# BB-8_Dome_FX_Module.net
KiCad netlist of a schematic drawn in EAGLE
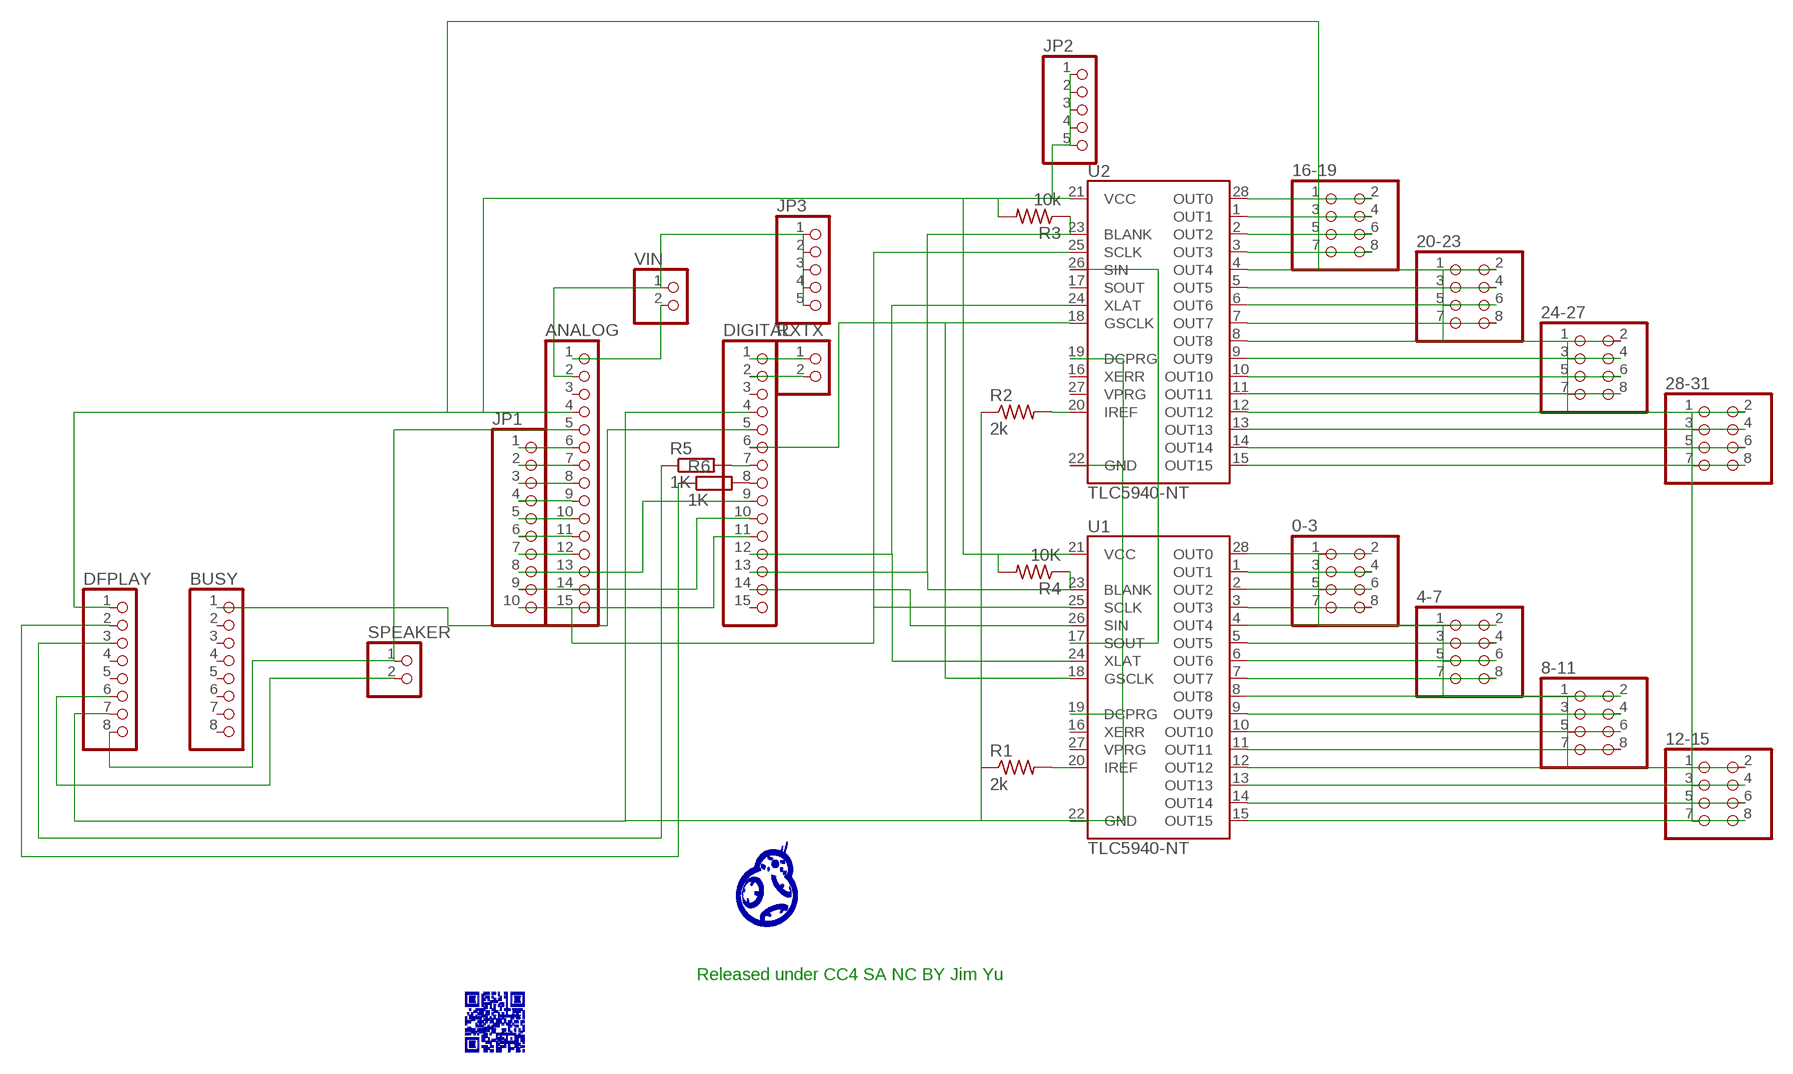
[diagram p0: schematic, sheet 1]

(export (version "E")
  (design (tool "Eeschema 10.0.6"))
  (components
    (comp (ref "0-3")
      (value "PINHD-2X4")
      (footprint "eagle-import:2X04")
      (libsource (lib "eagle-import") (part "PINHD-2X4"))
    )
    (comp (ref "4-7")
      (value "PINHD-2X4")
      (footprint "eagle-import:2X04")
      (libsource (lib "eagle-import") (part "PINHD-2X4"))
    )
    (comp (ref "8-11")
      (value "PINHD-2X4")
      (footprint "eagle-import:2X04")
      (libsource (lib "eagle-import") (part "PINHD-2X4"))
    )
    (comp (ref "12-15")
      (value "PINHD-2X4")
      (footprint "eagle-import:2X04")
      (libsource (lib "eagle-import") (part "PINHD-2X4"))
    )
    (comp (ref "16-19")
      (value "PINHD-2X4")
      (footprint "eagle-import:2X04")
      (libsource (lib "eagle-import") (part "PINHD-2X4"))
    )
    (comp (ref "20-23")
      (value "PINHD-2X4")
      (footprint "eagle-import:2X04")
      (libsource (lib "eagle-import") (part "PINHD-2X4"))
    )
    (comp (ref "24-27")
      (value "PINHD-2X4")
      (footprint "eagle-import:2X04")
      (libsource (lib "eagle-import") (part "PINHD-2X4"))
    )
    (comp (ref "28-31")
      (value "PINHD-2X4")
      (footprint "eagle-import:2X04")
      (libsource (lib "eagle-import") (part "PINHD-2X4"))
    )
    (comp (ref "ANALOG")
      (value "PINHD-1X15")
      (footprint "eagle-import:1X15")
      (libsource (lib "eagle-import") (part "PINHD-1X15"))
    )
    (comp (ref "BUSY")
      (value "PINHD-1X8")
      (footprint "eagle-import:1X08")
      (libsource (lib "eagle-import") (part "PINHD-1X8"))
    )
    (comp (ref "DFPLAY")
      (value "PINHD-1X8")
      (footprint "eagle-import:1X08")
      (libsource (lib "eagle-import") (part "PINHD-1X8"))
    )
    (comp (ref "DIGITAL")
      (value "PINHD-1X15")
      (footprint "eagle-import:1X15")
      (libsource (lib "eagle-import") (part "PINHD-1X15"))
    )
    (comp (ref "JP1")
      (value "PINHD-1X10")
      (footprint "eagle-import:1X10")
      (libsource (lib "eagle-import") (part "PINHD-1X10"))
    )
    (comp (ref "JP2")
      (value "PINHD-1X5")
      (footprint "eagle-import:1X05")
      (libsource (lib "eagle-import") (part "PINHD-1X5"))
    )
    (comp (ref "JP3")
      (value "PINHD-1X5")
      (footprint "eagle-import:1X05")
      (libsource (lib "eagle-import") (part "PINHD-1X5"))
    )
    (comp (ref "R1")
      (value "2k")
      (footprint "eagle-import:0204_5")
      (libsource (lib "eagle-import") (part "R-US_0204/5"))
    )
    (comp (ref "R2")
      (value "2k")
      (footprint "eagle-import:0204_5")
      (libsource (lib "eagle-import") (part "R-US_0204/5"))
    )
    (comp (ref "R3")
      (value "10k")
      (footprint "eagle-import:0204_5")
      (libsource (lib "eagle-import") (part "R-US_0204/5"))
    )
    (comp (ref "R4")
      (value "10K")
      (footprint "eagle-import:0204_5")
      (libsource (lib "eagle-import") (part "R-US_0204/5"))
    )
    (comp (ref "R5")
      (value "1K")
      (footprint "eagle-import:0204_5")
      (libsource (lib "eagle-import") (part "R-EU_0204/5"))
    )
    (comp (ref "R6")
      (value "1K")
      (footprint "eagle-import:0204_5")
      (libsource (lib "eagle-import") (part "R-EU_0204/5"))
    )
    (comp (ref "RXTX")
      (value "PINHD-1X2")
      (footprint "eagle-import:1X02")
      (libsource (lib "eagle-import") (part "PINHD-1X2"))
    )
    (comp (ref "SPEAKER")
      (value "PINHD-1X2")
      (footprint "eagle-import:1X02")
      (libsource (lib "eagle-import") (part "PINHD-1X2"))
    )
    (comp (ref "U1")
      (value "TLC5940-NT")
      (footprint "eagle-import:DIL28-3")
      (libsource (lib "eagle-import") (part "TLC5940-NT"))
    )
    (comp (ref "U2")
      (value "TLC5940-NT")
      (footprint "eagle-import:DIL28-3")
      (libsource (lib "eagle-import") (part "TLC5940-NT"))
    )
    (comp (ref "VIN")
      (value "PINHD-1X2")
      (footprint "eagle-import:1X02")
      (libsource (lib "eagle-import") (part "PINHD-1X2"))
    )
  )
  (nets
    (net (code "1") (name "Net-(ANALOG-Pad1)") (class "Default")
      (node (ref "ANALOG") (pin "1") (pinfunction "1_1") (pintype "passive"))
      (node (ref "VIN") (pin "2") (pinfunction "2_2") (pintype "passive"))
    )
    (net (code "2") (name "Net-(ANALOG-Pad2)") (class "Default")
      (node (ref "ANALOG") (pin "2") (pinfunction "2_2") (pintype "passive"))
      (node (ref "JP3") (pin "1") (pinfunction "1_1") (pintype "passive"))
      (node (ref "JP3") (pin "2") (pinfunction "2_2") (pintype "passive"))
      (node (ref "JP3") (pin "3") (pinfunction "3_3") (pintype "passive"))
      (node (ref "JP3") (pin "4") (pinfunction "4_4") (pintype "passive"))
      (node (ref "JP3") (pin "5") (pinfunction "5_5") (pintype "passive"))
      (node (ref "VIN") (pin "1") (pinfunction "1_1") (pintype "passive"))
    )
    (net (code "3") (name "Net-(ANALOG-Pad5)") (class "Default")
      (node (ref "ANALOG") (pin "5") (pinfunction "5_5") (pintype "passive"))
      (node (ref "DFPLAY") (pin "8") (pinfunction "8_8") (pintype "passive"))
      (node (ref "SPEAKER") (pin "1") (pinfunction "1_1") (pintype "passive"))
    )
    (net (code "4") (name "Net-(ANALOG-Pad6)") (class "Default")
      (node (ref "ANALOG") (pin "6") (pinfunction "6_6") (pintype "passive"))
      (node (ref "JP1") (pin "1") (pinfunction "1_1") (pintype "passive"))
    )
    (net (code "5") (name "Net-(ANALOG-Pad7)") (class "Default")
      (node (ref "ANALOG") (pin "7") (pinfunction "7_7") (pintype "passive"))
      (node (ref "JP1") (pin "2") (pinfunction "2_2") (pintype "passive"))
    )
    (net (code "6") (name "Net-(ANALOG-Pad8)") (class "Default")
      (node (ref "ANALOG") (pin "8") (pinfunction "8_8") (pintype "passive"))
      (node (ref "JP1") (pin "3") (pinfunction "3_3") (pintype "passive"))
    )
    (net (code "7") (name "Net-(ANALOG-Pad9)") (class "Default")
      (node (ref "ANALOG") (pin "9") (pinfunction "9_9") (pintype "passive"))
      (node (ref "JP1") (pin "4") (pinfunction "4_4") (pintype "passive"))
    )
    (net (code "8") (name "Net-(ANALOG-Pad10)") (class "Default")
      (node (ref "ANALOG") (pin "10") (pinfunction "10_10") (pintype "passive"))
      (node (ref "JP1") (pin "5") (pinfunction "5_5") (pintype "passive"))
    )
    (net (code "9") (name "Net-(ANALOG-Pad11)") (class "Default")
      (node (ref "ANALOG") (pin "11") (pinfunction "11_11") (pintype "passive"))
      (node (ref "JP1") (pin "6") (pinfunction "6_6") (pintype "passive"))
    )
    (net (code "10") (name "Net-(ANALOG-Pad12)") (class "Default")
      (node (ref "ANALOG") (pin "12") (pinfunction "12_12") (pintype "passive"))
      (node (ref "JP1") (pin "7") (pinfunction "7_7") (pintype "passive"))
    )
    (net (code "11") (name "Net-(BUSY-Pad1)") (class "Default")
      (node (ref "BUSY") (pin "1") (pinfunction "1_1") (pintype "passive"))
      (node (ref "DIGITAL") (pin "5") (pinfunction "5_5") (pintype "passive"))
    )
    (net (code "12") (name "Net-(DFPLAY-Pad2)") (class "Default")
      (node (ref "DFPLAY") (pin "2") (pinfunction "2_2") (pintype "passive"))
      (node (ref "R6") (pin "1") (pinfunction "1_1") (pintype "passive"))
    )
    (net (code "13") (name "Net-(DFPLAY-Pad3)") (class "Default")
      (node (ref "DFPLAY") (pin "3") (pinfunction "3_3") (pintype "passive"))
      (node (ref "R5") (pin "1") (pinfunction "1_1") (pintype "passive"))
    )
    (net (code "14") (name "Net-(DFPLAY-Pad6)") (class "Default")
      (node (ref "DFPLAY") (pin "6") (pinfunction "6_6") (pintype "passive"))
      (node (ref "SPEAKER") (pin "2") (pinfunction "2_2") (pintype "passive"))
    )
    (net (code "15") (name "Net-(DIGITAL-Pad1)") (class "Default")
      (node (ref "DIGITAL") (pin "1") (pinfunction "1_1") (pintype "passive"))
      (node (ref "RXTX") (pin "1") (pinfunction "1_1") (pintype "passive"))
    )
    (net (code "16") (name "Net-(DIGITAL-Pad2)") (class "Default")
      (node (ref "DIGITAL") (pin "2") (pinfunction "2_2") (pintype "passive"))
      (node (ref "RXTX") (pin "2") (pinfunction "2_2") (pintype "passive"))
    )
    (net (code "17") (name "Net-(DIGITAL-Pad7)") (class "Default")
      (node (ref "DIGITAL") (pin "7") (pinfunction "7_7") (pintype "passive"))
      (node (ref "R5") (pin "2") (pinfunction "2_2") (pintype "passive"))
    )
    (net (code "18") (name "Net-(DIGITAL-Pad8)") (class "Default")
      (node (ref "DIGITAL") (pin "8") (pinfunction "8_8") (pintype "passive"))
      (node (ref "R6") (pin "2") (pinfunction "2_2") (pintype "passive"))
    )
    (net (code "19") (name "Net-(DIGITAL-Pad9)") (class "Default")
      (node (ref "DIGITAL") (pin "9") (pinfunction "9_9") (pintype "passive"))
      (node (ref "JP1") (pin "8") (pinfunction "8_8") (pintype "passive"))
    )
    (net (code "20") (name "Net-(DIGITAL-Pad10)") (class "Default")
      (node (ref "DIGITAL") (pin "10") (pinfunction "10_10") (pintype "passive"))
      (node (ref "JP1") (pin "9") (pinfunction "9_9") (pintype "passive"))
    )
    (net (code "21") (name "Net-(DIGITAL-Pad11)") (class "Default")
      (node (ref "DIGITAL") (pin "11") (pinfunction "11_11") (pintype "passive"))
      (node (ref "JP1") (pin "10") (pinfunction "10_10") (pintype "passive"))
    )
    (net (code "22") (name "Net-(U1-BLANK)") (class "Default")
      (node (ref "DIGITAL") (pin "13") (pinfunction "13_13") (pintype "passive"))
      (node (ref "R3") (pin "1") (pinfunction "1_1") (pintype "passive"))
      (node (ref "R4") (pin "1") (pinfunction "1_1") (pintype "passive"))
      (node (ref "U1") (pin "23") (pinfunction "BLANK_23") (pintype "bidirectional"))
      (node (ref "U2") (pin "23") (pinfunction "BLANK_23") (pintype "bidirectional"))
    )
    (net (code "23") (name "Net-(U1-DCPRG)") (class "Default")
      (node (ref "DFPLAY") (pin "7") (pinfunction "7_7") (pintype "passive"))
      (node (ref "DIGITAL") (pin "4") (pinfunction "4_4") (pintype "passive"))
      (node (ref "R1") (pin "1") (pinfunction "1_1") (pintype "passive"))
      (node (ref "R2") (pin "1") (pinfunction "1_1") (pintype "passive"))
      (node (ref "U1") (pin "19") (pinfunction "DCPRG_19") (pintype "bidirectional"))
      (node (ref "U1") (pin "22") (pinfunction "GND_22") (pintype "bidirectional"))
      (node (ref "U2") (pin "19") (pinfunction "DCPRG_19") (pintype "bidirectional"))
      (node (ref "U2") (pin "22") (pinfunction "GND_22") (pintype "bidirectional"))
    )
    (net (code "24") (name "Net-(U1-GSCLK)") (class "Default")
      (node (ref "DIGITAL") (pin "6") (pinfunction "6_6") (pintype "passive"))
      (node (ref "U1") (pin "18") (pinfunction "GSCLK_18") (pintype "bidirectional"))
      (node (ref "U2") (pin "18") (pinfunction "GSCLK_18") (pintype "bidirectional"))
    )
    (net (code "25") (name "Net-(U1-IREF)") (class "Default")
      (node (ref "R1") (pin "2") (pinfunction "2_2") (pintype "passive"))
      (node (ref "U1") (pin "20") (pinfunction "IREF_20") (pintype "bidirectional"))
    )
    (net (code "26") (name "Net-(U1-OUT0)") (class "Default")
      (node (ref "0-3") (pin "2") (pinfunction "2_2") (pintype "passive"))
      (node (ref "U1") (pin "28") (pinfunction "OUT0_28") (pintype "bidirectional"))
    )
    (net (code "27") (name "Net-(U1-OUT1)") (class "Default")
      (node (ref "0-3") (pin "4") (pinfunction "4_4") (pintype "passive"))
      (node (ref "U1") (pin "1") (pinfunction "OUT1_1") (pintype "bidirectional"))
    )
    (net (code "28") (name "Net-(U1-OUT2)") (class "Default")
      (node (ref "0-3") (pin "6") (pinfunction "6_6") (pintype "passive"))
      (node (ref "U1") (pin "2") (pinfunction "OUT2_2") (pintype "bidirectional"))
    )
    (net (code "29") (name "Net-(U1-OUT3)") (class "Default")
      (node (ref "0-3") (pin "8") (pinfunction "8_8") (pintype "passive"))
      (node (ref "U1") (pin "3") (pinfunction "OUT3_3") (pintype "bidirectional"))
    )
    (net (code "30") (name "Net-(U1-OUT4)") (class "Default")
      (node (ref "4-7") (pin "2") (pinfunction "2_2") (pintype "passive"))
      (node (ref "U1") (pin "4") (pinfunction "OUT4_4") (pintype "bidirectional"))
    )
    (net (code "31") (name "Net-(U1-OUT5)") (class "Default")
      (node (ref "4-7") (pin "4") (pinfunction "4_4") (pintype "passive"))
      (node (ref "U1") (pin "5") (pinfunction "OUT5_5") (pintype "bidirectional"))
    )
    (net (code "32") (name "Net-(U1-OUT6)") (class "Default")
      (node (ref "4-7") (pin "6") (pinfunction "6_6") (pintype "passive"))
      (node (ref "U1") (pin "6") (pinfunction "OUT6_6") (pintype "bidirectional"))
    )
    (net (code "33") (name "Net-(U1-OUT7)") (class "Default")
      (node (ref "4-7") (pin "8") (pinfunction "8_8") (pintype "passive"))
      (node (ref "U1") (pin "7") (pinfunction "OUT7_7") (pintype "bidirectional"))
    )
    (net (code "34") (name "Net-(U1-OUT8)") (class "Default")
      (node (ref "8-11") (pin "2") (pinfunction "2_2") (pintype "passive"))
      (node (ref "U1") (pin "8") (pinfunction "OUT8_8") (pintype "bidirectional"))
    )
    (net (code "35") (name "Net-(U1-OUT9)") (class "Default")
      (node (ref "8-11") (pin "4") (pinfunction "4_4") (pintype "passive"))
      (node (ref "U1") (pin "9") (pinfunction "OUT9_9") (pintype "bidirectional"))
    )
    (net (code "36") (name "Net-(U1-OUT10)") (class "Default")
      (node (ref "8-11") (pin "6") (pinfunction "6_6") (pintype "passive"))
      (node (ref "U1") (pin "10") (pinfunction "OUT10_10") (pintype "bidirectional"))
    )
    (net (code "37") (name "Net-(U1-OUT11)") (class "Default")
      (node (ref "8-11") (pin "8") (pinfunction "8_8") (pintype "passive"))
      (node (ref "U1") (pin "11") (pinfunction "OUT11_11") (pintype "bidirectional"))
    )
    (net (code "38") (name "Net-(U1-OUT12)") (class "Default")
      (node (ref "12-15") (pin "2") (pinfunction "2_2") (pintype "passive"))
      (node (ref "U1") (pin "12") (pinfunction "OUT12_12") (pintype "bidirectional"))
    )
    (net (code "39") (name "Net-(U1-OUT13)") (class "Default")
      (node (ref "12-15") (pin "4") (pinfunction "4_4") (pintype "passive"))
      (node (ref "U1") (pin "13") (pinfunction "OUT13_13") (pintype "bidirectional"))
    )
    (net (code "40") (name "Net-(U1-OUT14)") (class "Default")
      (node (ref "12-15") (pin "6") (pinfunction "6_6") (pintype "passive"))
      (node (ref "U1") (pin "14") (pinfunction "OUT14_14") (pintype "bidirectional"))
    )
    (net (code "41") (name "Net-(U1-OUT15)") (class "Default")
      (node (ref "12-15") (pin "8") (pinfunction "8_8") (pintype "passive"))
      (node (ref "U1") (pin "15") (pinfunction "OUT15_15") (pintype "bidirectional"))
    )
    (net (code "42") (name "Net-(U1-SCLK)") (class "Default")
      (node (ref "ANALOG") (pin "15") (pinfunction "15_15") (pintype "passive"))
      (node (ref "U1") (pin "25") (pinfunction "SCLK_25") (pintype "bidirectional"))
      (node (ref "U2") (pin "25") (pinfunction "SCLK_25") (pintype "bidirectional"))
    )
    (net (code "43") (name "Net-(U1-SIN)") (class "Default")
      (node (ref "DIGITAL") (pin "14") (pinfunction "14_14") (pintype "passive"))
      (node (ref "U1") (pin "26") (pinfunction "SIN_26") (pintype "bidirectional"))
    )
    (net (code "44") (name "Net-(U1-SOUT)") (class "Default")
      (node (ref "U1") (pin "17") (pinfunction "SOUT_17") (pintype "bidirectional"))
      (node (ref "U2") (pin "26") (pinfunction "SIN_26") (pintype "bidirectional"))
    )
    (net (code "45") (name "Net-(U1-VCC)") (class "Default")
      (node (ref "0-3") (pin "1") (pinfunction "1_1") (pintype "passive"))
      (node (ref "0-3") (pin "3") (pinfunction "3_3") (pintype "passive"))
      (node (ref "0-3") (pin "5") (pinfunction "5_5") (pintype "passive"))
      (node (ref "0-3") (pin "7") (pinfunction "7_7") (pintype "passive"))
      (node (ref "12-15") (pin "1") (pinfunction "1_1") (pintype "passive"))
      (node (ref "12-15") (pin "3") (pinfunction "3_3") (pintype "passive"))
      (node (ref "12-15") (pin "5") (pinfunction "5_5") (pintype "passive"))
      (node (ref "12-15") (pin "7") (pinfunction "7_7") (pintype "passive"))
      (node (ref "16-19") (pin "1") (pinfunction "1_1") (pintype "passive"))
      (node (ref "16-19") (pin "3") (pinfunction "3_3") (pintype "passive"))
      (node (ref "16-19") (pin "5") (pinfunction "5_5") (pintype "passive"))
      (node (ref "16-19") (pin "7") (pinfunction "7_7") (pintype "passive"))
      (node (ref "20-23") (pin "1") (pinfunction "1_1") (pintype "passive"))
      (node (ref "20-23") (pin "3") (pinfunction "3_3") (pintype "passive"))
      (node (ref "20-23") (pin "5") (pinfunction "5_5") (pintype "passive"))
      (node (ref "20-23") (pin "7") (pinfunction "7_7") (pintype "passive"))
      (node (ref "24-27") (pin "1") (pinfunction "1_1") (pintype "passive"))
      (node (ref "24-27") (pin "3") (pinfunction "3_3") (pintype "passive"))
      (node (ref "24-27") (pin "5") (pinfunction "5_5") (pintype "passive"))
      (node (ref "24-27") (pin "7") (pinfunction "7_7") (pintype "passive"))
      (node (ref "28-31") (pin "1") (pinfunction "1_1") (pintype "passive"))
      (node (ref "28-31") (pin "3") (pinfunction "3_3") (pintype "passive"))
      (node (ref "28-31") (pin "5") (pinfunction "5_5") (pintype "passive"))
      (node (ref "28-31") (pin "7") (pinfunction "7_7") (pintype "passive"))
      (node (ref "4-7") (pin "1") (pinfunction "1_1") (pintype "passive"))
      (node (ref "4-7") (pin "3") (pinfunction "3_3") (pintype "passive"))
      (node (ref "4-7") (pin "5") (pinfunction "5_5") (pintype "passive"))
      (node (ref "4-7") (pin "7") (pinfunction "7_7") (pintype "passive"))
      (node (ref "8-11") (pin "1") (pinfunction "1_1") (pintype "passive"))
      (node (ref "8-11") (pin "3") (pinfunction "3_3") (pintype "passive"))
      (node (ref "8-11") (pin "5") (pinfunction "5_5") (pintype "passive"))
      (node (ref "8-11") (pin "7") (pinfunction "7_7") (pintype "passive"))
      (node (ref "ANALOG") (pin "4") (pinfunction "4_4") (pintype "passive"))
      (node (ref "DFPLAY") (pin "1") (pinfunction "1_1") (pintype "passive"))
      (node (ref "JP2") (pin "1") (pinfunction "1_1") (pintype "passive"))
      (node (ref "JP2") (pin "2") (pinfunction "2_2") (pintype "passive"))
      (node (ref "JP2") (pin "3") (pinfunction "3_3") (pintype "passive"))
      (node (ref "JP2") (pin "4") (pinfunction "4_4") (pintype "passive"))
      (node (ref "JP2") (pin "5") (pinfunction "5_5") (pintype "passive"))
      (node (ref "R3") (pin "2") (pinfunction "2_2") (pintype "passive"))
      (node (ref "R4") (pin "2") (pinfunction "2_2") (pintype "passive"))
      (node (ref "U1") (pin "21") (pinfunction "VCC_21") (pintype "bidirectional"))
      (node (ref "U2") (pin "21") (pinfunction "VCC_21") (pintype "bidirectional"))
    )
    (net (code "46") (name "Net-(U1-XLAT)") (class "Default")
      (node (ref "DIGITAL") (pin "12") (pinfunction "12_12") (pintype "passive"))
      (node (ref "U1") (pin "24") (pinfunction "XLAT_24") (pintype "bidirectional"))
      (node (ref "U2") (pin "24") (pinfunction "XLAT_24") (pintype "bidirectional"))
    )
    (net (code "47") (name "Net-(U2-IREF)") (class "Default")
      (node (ref "R2") (pin "2") (pinfunction "2_2") (pintype "passive"))
      (node (ref "U2") (pin "20") (pinfunction "IREF_20") (pintype "bidirectional"))
    )
    (net (code "48") (name "Net-(U2-OUT0)") (class "Default")
      (node (ref "16-19") (pin "2") (pinfunction "2_2") (pintype "passive"))
      (node (ref "U2") (pin "28") (pinfunction "OUT0_28") (pintype "bidirectional"))
    )
    (net (code "49") (name "Net-(U2-OUT1)") (class "Default")
      (node (ref "16-19") (pin "4") (pinfunction "4_4") (pintype "passive"))
      (node (ref "U2") (pin "1") (pinfunction "OUT1_1") (pintype "bidirectional"))
    )
    (net (code "50") (name "Net-(U2-OUT2)") (class "Default")
      (node (ref "16-19") (pin "6") (pinfunction "6_6") (pintype "passive"))
      (node (ref "U2") (pin "2") (pinfunction "OUT2_2") (pintype "bidirectional"))
    )
    (net (code "51") (name "Net-(U2-OUT3)") (class "Default")
      (node (ref "16-19") (pin "8") (pinfunction "8_8") (pintype "passive"))
      (node (ref "U2") (pin "3") (pinfunction "OUT3_3") (pintype "bidirectional"))
    )
    (net (code "52") (name "Net-(U2-OUT4)") (class "Default")
      (node (ref "20-23") (pin "2") (pinfunction "2_2") (pintype "passive"))
      (node (ref "U2") (pin "4") (pinfunction "OUT4_4") (pintype "bidirectional"))
    )
    (net (code "53") (name "Net-(U2-OUT5)") (class "Default")
      (node (ref "20-23") (pin "4") (pinfunction "4_4") (pintype "passive"))
      (node (ref "U2") (pin "5") (pinfunction "OUT5_5") (pintype "bidirectional"))
    )
    (net (code "54") (name "Net-(U2-OUT6)") (class "Default")
      (node (ref "20-23") (pin "6") (pinfunction "6_6") (pintype "passive"))
      (node (ref "U2") (pin "6") (pinfunction "OUT6_6") (pintype "bidirectional"))
    )
    (net (code "55") (name "Net-(U2-OUT7)") (class "Default")
      (node (ref "20-23") (pin "8") (pinfunction "8_8") (pintype "passive"))
      (node (ref "U2") (pin "7") (pinfunction "OUT7_7") (pintype "bidirectional"))
    )
    (net (code "56") (name "Net-(U2-OUT8)") (class "Default")
      (node (ref "24-27") (pin "2") (pinfunction "2_2") (pintype "passive"))
      (node (ref "U2") (pin "8") (pinfunction "OUT8_8") (pintype "bidirectional"))
    )
    (net (code "57") (name "Net-(U2-OUT9)") (class "Default")
      (node (ref "24-27") (pin "4") (pinfunction "4_4") (pintype "passive"))
      (node (ref "U2") (pin "9") (pinfunction "OUT9_9") (pintype "bidirectional"))
    )
    (net (code "58") (name "Net-(U2-OUT10)") (class "Default")
      (node (ref "24-27") (pin "6") (pinfunction "6_6") (pintype "passive"))
      (node (ref "U2") (pin "10") (pinfunction "OUT10_10") (pintype "bidirectional"))
    )
    (net (code "59") (name "Net-(U2-OUT11)") (class "Default")
      (node (ref "24-27") (pin "8") (pinfunction "8_8") (pintype "passive"))
      (node (ref "U2") (pin "11") (pinfunction "OUT11_11") (pintype "bidirectional"))
    )
    (net (code "60") (name "Net-(U2-OUT12)") (class "Default")
      (node (ref "28-31") (pin "2") (pinfunction "2_2") (pintype "passive"))
      (node (ref "U2") (pin "12") (pinfunction "OUT12_12") (pintype "bidirectional"))
    )
    (net (code "61") (name "Net-(U2-OUT13)") (class "Default")
      (node (ref "28-31") (pin "4") (pinfunction "4_4") (pintype "passive"))
      (node (ref "U2") (pin "13") (pinfunction "OUT13_13") (pintype "bidirectional"))
    )
    (net (code "62") (name "Net-(U2-OUT14)") (class "Default")
      (node (ref "28-31") (pin "6") (pinfunction "6_6") (pintype "passive"))
      (node (ref "U2") (pin "14") (pinfunction "OUT14_14") (pintype "bidirectional"))
    )
    (net (code "63") (name "Net-(U2-OUT15)") (class "Default")
      (node (ref "28-31") (pin "8") (pinfunction "8_8") (pintype "passive"))
      (node (ref "U2") (pin "15") (pinfunction "OUT15_15") (pintype "bidirectional"))
    )
    (net (code "64") (name "unconnected-(ANALOG-Pad3)") (class "Default")
      (node (ref "ANALOG") (pin "3") (pinfunction "3_3") (pintype "passive"))
    )
    (net (code "65") (name "unconnected-(ANALOG-Pad13)") (class "Default")
      (node (ref "ANALOG") (pin "13") (pinfunction "13_13") (pintype "passive"))
    )
    (net (code "66") (name "unconnected-(ANALOG-Pad14)") (class "Default")
      (node (ref "ANALOG") (pin "14") (pinfunction "14_14") (pintype "passive"))
    )
    (net (code "67") (name "unconnected-(BUSY-Pad2)") (class "Default")
      (node (ref "BUSY") (pin "2") (pinfunction "2_2") (pintype "passive"))
    )
    (net (code "68") (name "unconnected-(BUSY-Pad3)") (class "Default")
      (node (ref "BUSY") (pin "3") (pinfunction "3_3") (pintype "passive"))
    )
    (net (code "69") (name "unconnected-(BUSY-Pad4)") (class "Default")
      (node (ref "BUSY") (pin "4") (pinfunction "4_4") (pintype "passive"))
    )
    (net (code "70") (name "unconnected-(BUSY-Pad5)") (class "Default")
      (node (ref "BUSY") (pin "5") (pinfunction "5_5") (pintype "passive"))
    )
    (net (code "71") (name "unconnected-(BUSY-Pad6)") (class "Default")
      (node (ref "BUSY") (pin "6") (pinfunction "6_6") (pintype "passive"))
    )
    (net (code "72") (name "unconnected-(BUSY-Pad7)") (class "Default")
      (node (ref "BUSY") (pin "7") (pinfunction "7_7") (pintype "passive"))
    )
    (net (code "73") (name "unconnected-(BUSY-Pad8)") (class "Default")
      (node (ref "BUSY") (pin "8") (pinfunction "8_8") (pintype "passive"))
    )
    (net (code "74") (name "unconnected-(DFPLAY-Pad4)") (class "Default")
      (node (ref "DFPLAY") (pin "4") (pinfunction "4_4") (pintype "passive"))
    )
    (net (code "75") (name "unconnected-(DFPLAY-Pad5)") (class "Default")
      (node (ref "DFPLAY") (pin "5") (pinfunction "5_5") (pintype "passive"))
    )
    (net (code "76") (name "unconnected-(DIGITAL-Pad3)") (class "Default")
      (node (ref "DIGITAL") (pin "3") (pinfunction "3_3") (pintype "passive"))
    )
    (net (code "77") (name "unconnected-(DIGITAL-Pad15)") (class "Default")
      (node (ref "DIGITAL") (pin "15") (pinfunction "15_15") (pintype "passive"))
    )
    (net (code "78") (name "unconnected-(U1-VPRG-Pad27)") (class "Default")
      (node (ref "U1") (pin "27") (pinfunction "VPRG_27") (pintype "bidirectional"))
    )
    (net (code "79") (name "unconnected-(U1-XERR-Pad16)") (class "Default")
      (node (ref "U1") (pin "16") (pinfunction "XERR_16") (pintype "bidirectional"))
    )
    (net (code "80") (name "unconnected-(U2-SOUT-Pad17)") (class "Default")
      (node (ref "U2") (pin "17") (pinfunction "SOUT_17") (pintype "bidirectional"))
    )
    (net (code "81") (name "unconnected-(U2-VPRG-Pad27)") (class "Default")
      (node (ref "U2") (pin "27") (pinfunction "VPRG_27") (pintype "bidirectional"))
    )
    (net (code "82") (name "unconnected-(U2-XERR-Pad16)") (class "Default")
      (node (ref "U2") (pin "16") (pinfunction "XERR_16") (pintype "bidirectional"))
    )
  )
)
